# SensorIoT_Node_Programmer.net
KiCad netlist of a schematic drawn in EAGLE
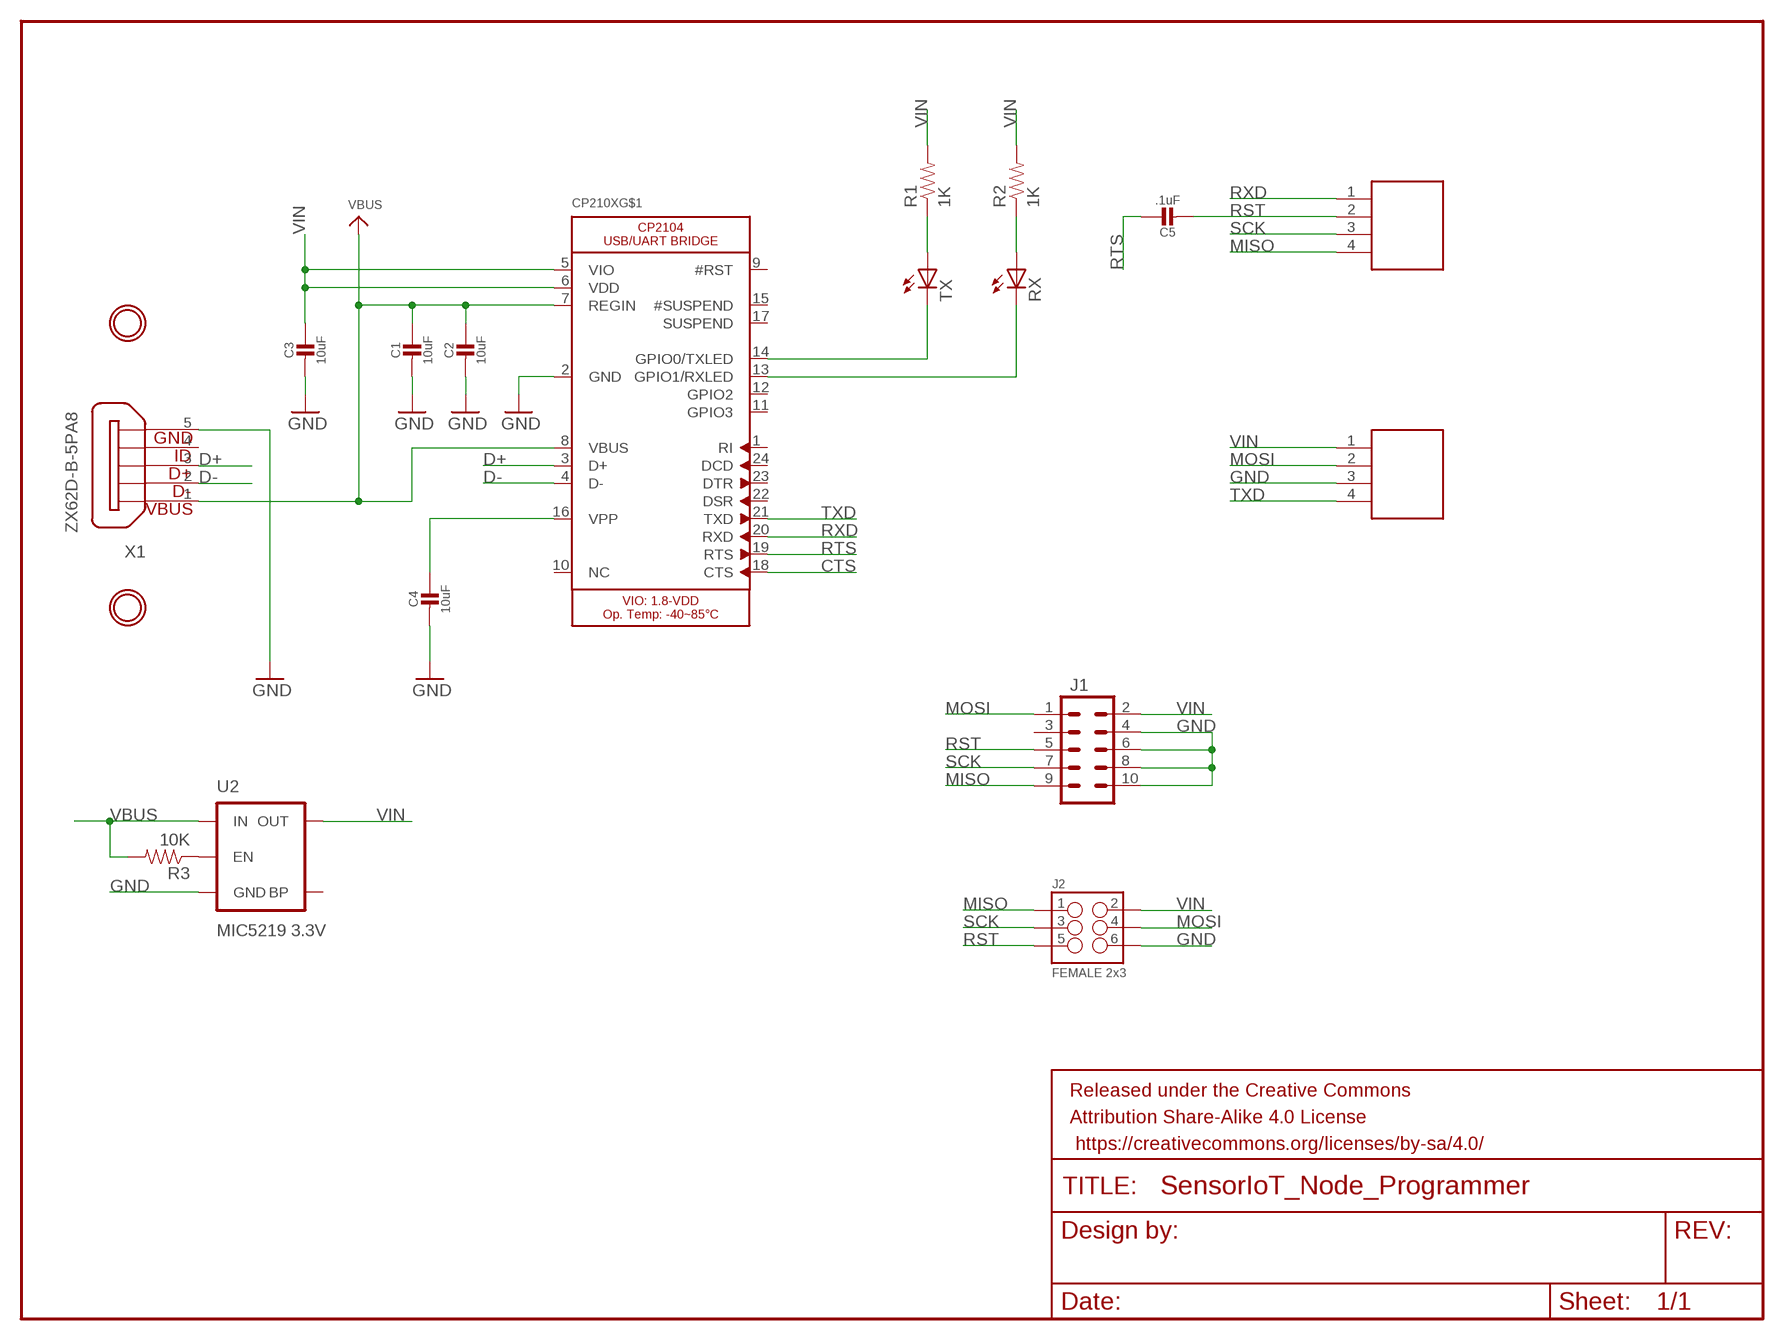
[diagram p0: schematic, sheet 1]

(export (version "E")
  (design (tool "Eeschema 10.0.6"))
  (components
    (comp (ref "C1")
      (value "10uF")
      (footprint "eagle-import:_0805")
      (libsource (lib "eagle-import") (part "CAP_CERAMIC_0805"))
    )
    (comp (ref "C2")
      (value "10uF")
      (footprint "eagle-import:_0805")
      (libsource (lib "eagle-import") (part "CAP_CERAMIC_0805"))
    )
    (comp (ref "C3")
      (value "10uF")
      (footprint "eagle-import:_0805")
      (libsource (lib "eagle-import") (part "CAP_CERAMIC_0805"))
    )
    (comp (ref "C4")
      (value "10uF")
      (footprint "eagle-import:_0805")
      (libsource (lib "eagle-import") (part "CAP_CERAMIC_0805"))
    )
    (comp (ref "C5")
      (value ".1uF")
      (footprint "eagle-import:_0805")
      (libsource (lib "eagle-import") (part "CAP_CERAMIC_0805"))
    )
    (comp (ref "CP210X")
      (value "CP2104")
      (footprint "eagle-import:QFN24_4MM_SMSC")
      (libsource (lib "eagle-import") (part "CP2104"))
    )
    (comp (ref "FRAME1")
      (value "FRAME-LETTER")
      (footprint "eagle-import:CREATIVE_COMMONS")
      (libsource (lib "eagle-import") (part "FRAME-LETTER"))
    )
    (comp (ref "J1")
      (value "M05X2PTH")
      (footprint "eagle-import:AVR_ICSP")
      (libsource (lib "eagle-import") (part "M05X2PTH"))
    )
    (comp (ref "J2")
      (value "FEMALE 2x3")
      (footprint "eagle-import:2X3")
      (libsource (lib "eagle-import") (part "M03X2FEMALE"))
    )
    (comp (ref "R1")
      (value "1K")
      (footprint "eagle-import:0805")
      (libsource (lib "eagle-import") (part "RESISTOR0805-RES"))
    )
    (comp (ref "R2")
      (value "1K")
      (footprint "eagle-import:0805")
      (libsource (lib "eagle-import") (part "RESISTOR0805-RES"))
    )
    (comp (ref "R3")
      (value "10K")
      (footprint "eagle-import:0805")
      (libsource (lib "eagle-import") (part "RESISTOR0805-RES"))
    )
    (comp (ref "RX")
      (value "LEDCHIP-LED0805")
      (footprint "eagle-import:CHIP-LED0805")
      (libsource (lib "eagle-import") (part "LEDCHIP-LED0805"))
    )
    (comp (ref "TX")
      (value "LEDCHIP-LED0805")
      (footprint "eagle-import:CHIP-LED0805")
      (libsource (lib "eagle-import") (part "LEDCHIP-LED0805"))
    )
    (comp (ref "U$2")
      (value "MOUNTINGHOLE2.0")
      (footprint "eagle-import:MOUNTINGHOLE_2.0_PLATED")
      (libsource (lib "eagle-import") (part "MOUNTINGHOLE2.0"))
    )
    (comp (ref "U$3")
      (value "MOUNTINGHOLE2.0")
      (footprint "eagle-import:MOUNTINGHOLE_2.0_PLATED")
      (libsource (lib "eagle-import") (part "MOUNTINGHOLE2.0"))
    )
    (comp (ref "U$4")
      (value "4X.1IN_POGO_PIN")
      (footprint "eagle-import:4X.1IN_POGO_PIN")
      (libsource (lib "eagle-import") (part "4X.1IN_POGO_PIN"))
    )
    (comp (ref "U$5")
      (value "4X.1IN_POGO_PIN")
      (footprint "eagle-import:4X.1IN_POGO_PIN")
      (libsource (lib "eagle-import") (part "4X.1IN_POGO_PIN"))
    )
    (comp (ref "U2")
      (value "MIC5219 3.3V")
      (footprint "eagle-import:SOT23-5")
      (libsource (lib "eagle-import") (part "V_REG_MIC52193.3V"))
    )
    (comp (ref "X1")
      (value "ZX62D-B-5PA8")
      (footprint "eagle-import:ZX62D-B-5PA8")
      (fields (field (name "MF") "Hirose"))
      (libsource (lib "eagle-import") (part "ZX62D-B-5PA8"))
    )
  )
  (nets
    (net (code "1") (name "/CTS") (class "Default")
      (node (ref "CP210X") (pin "18") (pinfunction "CTS_18") (pintype "input"))
    )
    (net (code "2") (name "/D+") (class "Default")
      (node (ref "CP210X") (pin "3") (pinfunction "D+_3") (pintype "bidirectional"))
      (node (ref "X1") (pin "3") (pinfunction "3_3") (pintype "passive"))
    )
    (net (code "3") (name "/D-") (class "Default")
      (node (ref "CP210X") (pin "4") (pinfunction "D-_4") (pintype "bidirectional"))
      (node (ref "X1") (pin "2") (pinfunction "2_2") (pintype "passive"))
    )
    (net (code "4") (name "/MISO") (class "Default")
      (node (ref "J1") (pin "9") (pinfunction "9_9") (pintype "passive"))
      (node (ref "J2") (pin "1") (pinfunction "1_1") (pintype "bidirectional"))
      (node (ref "U$4") (pin "4") (pinfunction "4_4") (pintype "bidirectional"))
    )
    (net (code "5") (name "/MOSI") (class "Default")
      (node (ref "J1") (pin "1") (pinfunction "1_1") (pintype "passive"))
      (node (ref "J2") (pin "4") (pinfunction "4_4") (pintype "bidirectional"))
      (node (ref "U$5") (pin "2") (pinfunction "2_2") (pintype "bidirectional"))
    )
    (net (code "6") (name "/RST") (class "Default")
      (node (ref "C5") (pin "2") (pinfunction "2_2") (pintype "passive"))
      (node (ref "J1") (pin "5") (pinfunction "5_5") (pintype "passive"))
      (node (ref "J2") (pin "5") (pinfunction "5_5") (pintype "bidirectional"))
      (node (ref "U$4") (pin "2") (pinfunction "2_2") (pintype "bidirectional"))
    )
    (net (code "7") (name "/RTS") (class "Default")
      (node (ref "C5") (pin "1") (pinfunction "1_1") (pintype "passive"))
      (node (ref "CP210X") (pin "19") (pinfunction "RTS_19") (pintype "output"))
    )
    (net (code "8") (name "/RXD") (class "Default")
      (node (ref "CP210X") (pin "20") (pinfunction "RXD_20") (pintype "input"))
      (node (ref "U$4") (pin "1") (pinfunction "1_1") (pintype "bidirectional"))
    )
    (net (code "9") (name "/SCK") (class "Default")
      (node (ref "J1") (pin "7") (pinfunction "7_7") (pintype "passive"))
      (node (ref "J2") (pin "3") (pinfunction "3_3") (pintype "bidirectional"))
      (node (ref "U$4") (pin "3") (pinfunction "3_3") (pintype "bidirectional"))
    )
    (net (code "10") (name "/TXD") (class "Default")
      (node (ref "CP210X") (pin "21") (pinfunction "TXD_21") (pintype "output"))
      (node (ref "U$5") (pin "4") (pinfunction "4_4") (pintype "bidirectional"))
    )
    (net (code "11") (name "/VIN") (class "Default")
      (node (ref "C3") (pin "1") (pinfunction "1_1") (pintype "passive"))
      (node (ref "CP210X") (pin "5") (pinfunction "VIO_5") (pintype "power_in"))
      (node (ref "CP210X") (pin "6") (pinfunction "VDD_6") (pintype "power_in"))
      (node (ref "J1") (pin "2") (pinfunction "2_2") (pintype "passive"))
      (node (ref "J2") (pin "2") (pinfunction "2_2") (pintype "bidirectional"))
      (node (ref "R1") (pin "2") (pinfunction "2_2") (pintype "passive"))
      (node (ref "R2") (pin "2") (pinfunction "2_2") (pintype "passive"))
      (node (ref "U$5") (pin "1") (pinfunction "1_1") (pintype "bidirectional"))
      (node (ref "U2") (pin "5") (pinfunction "OUT_5") (pintype "passive"))
    )
    (net (code "12") (name "GND") (class "Default")
      (node (ref "C1") (pin "2") (pinfunction "2_2") (pintype "passive"))
      (node (ref "C2") (pin "2") (pinfunction "2_2") (pintype "passive"))
      (node (ref "C3") (pin "2") (pinfunction "2_2") (pintype "passive"))
      (node (ref "C4") (pin "2") (pinfunction "2_2") (pintype "passive"))
      (node (ref "CP210X") (pin "2") (pinfunction "GND_2") (pintype "power_in"))
      (node (ref "J1") (pin "10") (pinfunction "10_10") (pintype "passive"))
      (node (ref "J1") (pin "4") (pinfunction "4_4") (pintype "passive"))
      (node (ref "J1") (pin "6") (pinfunction "6_6") (pintype "passive"))
      (node (ref "J1") (pin "8") (pinfunction "8_8") (pintype "passive"))
      (node (ref "J2") (pin "6") (pinfunction "6_6") (pintype "bidirectional"))
      (node (ref "U$5") (pin "3") (pinfunction "3_3") (pintype "bidirectional"))
      (node (ref "U2") (pin "2") (pinfunction "GND_2") (pintype "input"))
      (node (ref "X1") (pin "5") (pinfunction "5_5") (pintype "passive"))
    )
    (net (code "13") (name "Net-(CP210XA-GPIO0{slash}TXLED)") (class "Default")
      (node (ref "CP210X") (pin "14") (pinfunction "GPIO0/TXLED_14") (pintype "bidirectional"))
      (node (ref "TX") (pin "C") (pinfunction "C_C") (pintype "passive"))
    )
    (net (code "14") (name "Net-(CP210XA-GPIO1{slash}RXLED)") (class "Default")
      (node (ref "CP210X") (pin "13") (pinfunction "GPIO1/RXLED_13") (pintype "bidirectional"))
      (node (ref "RX") (pin "C") (pinfunction "C_C") (pintype "passive"))
    )
    (net (code "15") (name "Net-(CP210XA-VPP)") (class "Default")
      (node (ref "C4") (pin "1") (pinfunction "1_1") (pintype "passive"))
      (node (ref "CP210X") (pin "16") (pinfunction "VPP_16") (pintype "bidirectional"))
    )
    (net (code "16") (name "Net-(R1-Pad1)") (class "Default")
      (node (ref "R1") (pin "1") (pinfunction "1_1") (pintype "passive"))
      (node (ref "TX") (pin "A") (pinfunction "A_A") (pintype "passive"))
    )
    (net (code "17") (name "Net-(R2-Pad1)") (class "Default")
      (node (ref "R2") (pin "1") (pinfunction "1_1") (pintype "passive"))
      (node (ref "RX") (pin "A") (pinfunction "A_A") (pintype "passive"))
    )
    (net (code "18") (name "Net-(U2-EN)") (class "Default")
      (node (ref "R3") (pin "1") (pinfunction "1_1") (pintype "passive"))
      (node (ref "U2") (pin "3") (pinfunction "EN_3") (pintype "input"))
    )
    (net (code "19") (name "VBUS") (class "Default")
      (node (ref "C1") (pin "1") (pinfunction "1_1") (pintype "passive"))
      (node (ref "C2") (pin "1") (pinfunction "1_1") (pintype "passive"))
      (node (ref "CP210X") (pin "7") (pinfunction "REGIN_7") (pintype "power_in"))
      (node (ref "CP210X") (pin "8") (pinfunction "VBUS_8") (pintype "power_in"))
      (node (ref "R3") (pin "2") (pinfunction "2_2") (pintype "passive"))
      (node (ref "U2") (pin "1") (pinfunction "IN_1") (pintype "input"))
      (node (ref "X1") (pin "1") (pinfunction "1_1") (pintype "passive"))
    )
    (net (code "20") (name "unconnected-(CP210XA-#RST-Pad9)") (class "Default")
      (node (ref "CP210X") (pin "9") (pinfunction "#RST_9") (pintype "bidirectional"))
    )
    (net (code "21") (name "unconnected-(CP210XA-#SUSPEND-Pad15)") (class "Default")
      (node (ref "CP210X") (pin "15") (pinfunction "#SUSPEND_15") (pintype "output"))
    )
    (net (code "22") (name "unconnected-(CP210XA-DCD-Pad24)") (class "Default")
      (node (ref "CP210X") (pin "24") (pinfunction "DCD_24") (pintype "input"))
    )
    (net (code "23") (name "unconnected-(CP210XA-DSR-Pad22)") (class "Default")
      (node (ref "CP210X") (pin "22") (pinfunction "DSR_22") (pintype "input"))
    )
    (net (code "24") (name "unconnected-(CP210XA-DTR-Pad23)") (class "Default")
      (node (ref "CP210X") (pin "23") (pinfunction "DTR_23") (pintype "output"))
    )
    (net (code "25") (name "unconnected-(CP210XA-GPIO2-Pad12)") (class "Default")
      (node (ref "CP210X") (pin "12") (pinfunction "GPIO2_12") (pintype "bidirectional"))
    )
    (net (code "26") (name "unconnected-(CP210XA-GPIO3-Pad11)") (class "Default")
      (node (ref "CP210X") (pin "11") (pinfunction "GPIO3_11") (pintype "bidirectional"))
    )
    (net (code "27") (name "unconnected-(CP210XA-NC-Pad10)") (class "Default")
      (node (ref "CP210X") (pin "10") (pinfunction "NC_10") (pintype "no_connect"))
    )
    (net (code "28") (name "unconnected-(CP210XA-RI-Pad1)") (class "Default")
      (node (ref "CP210X") (pin "1") (pinfunction "RI_1") (pintype "input"))
    )
    (net (code "29") (name "unconnected-(CP210XA-SUSPEND-Pad17)") (class "Default")
      (node (ref "CP210X") (pin "17") (pinfunction "SUSPEND_17") (pintype "output"))
    )
    (net (code "30") (name "unconnected-(J1-Pad3)") (class "Default")
      (node (ref "J1") (pin "3") (pinfunction "3_3") (pintype "passive"))
    )
    (net (code "31") (name "unconnected-(U2-BP-Pad4)") (class "Default")
      (node (ref "U2") (pin "4") (pinfunction "BP_4") (pintype "input"))
    )
    (net (code "32") (name "unconnected-(X1-Pad4)") (class "Default")
      (node (ref "X1") (pin "4") (pinfunction "4_4") (pintype "passive"))
    )
  )
)
